# QFP_32U4.net
KiCad netlist of a schematic drawn in EAGLE
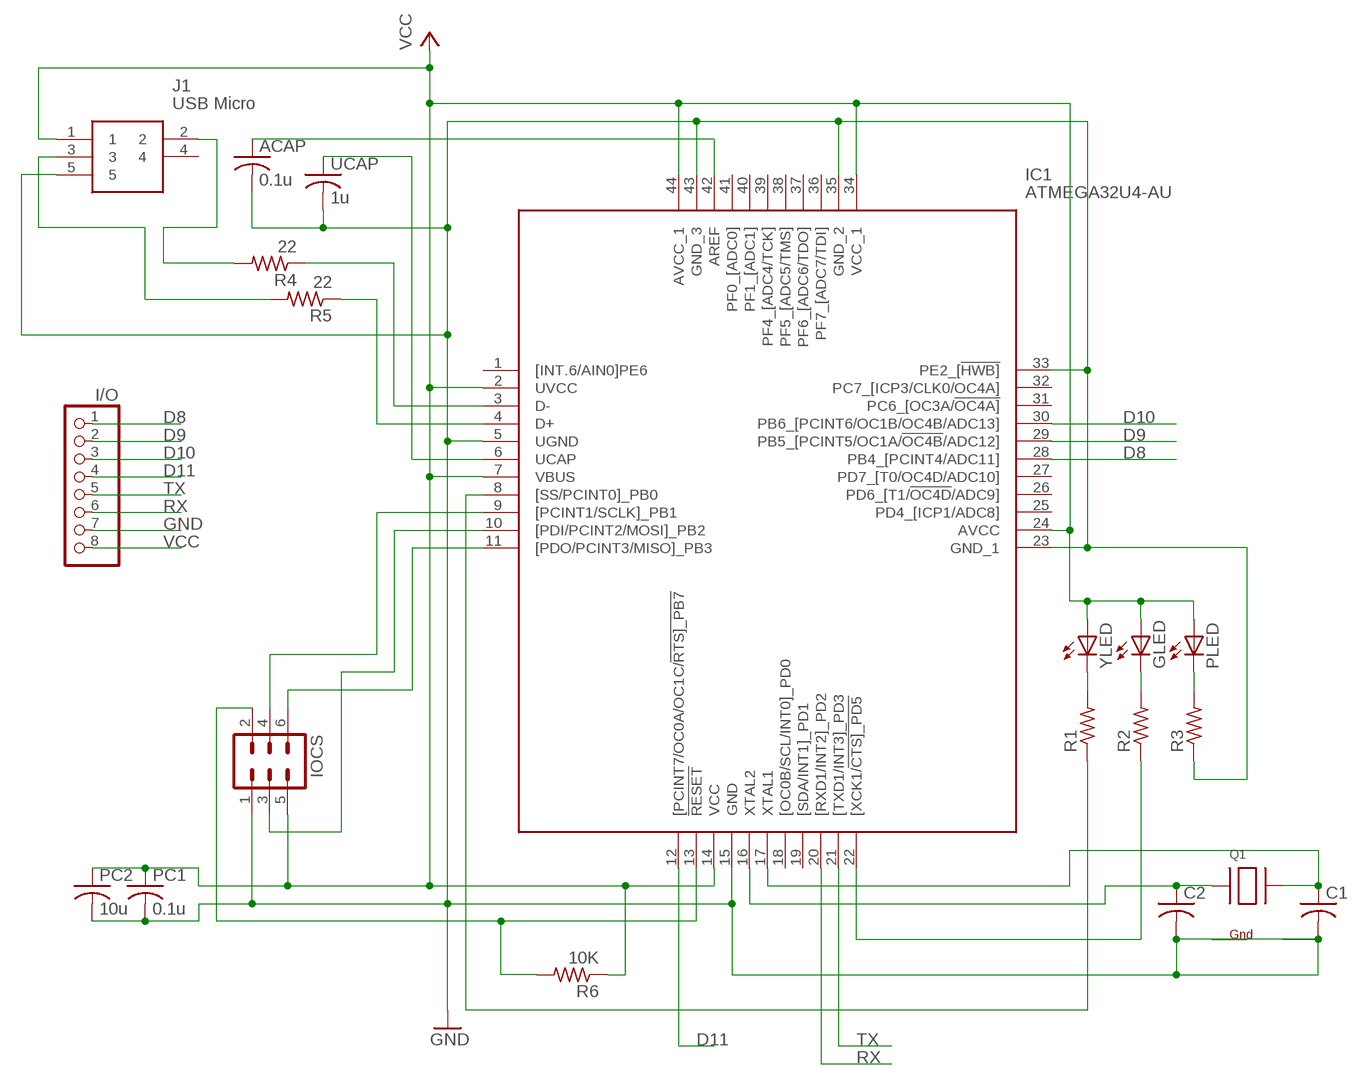
[diagram p0: schematic, sheet 1]

(export (version "E")
  (design (tool "Eeschema 10.0.6"))
  (components
    (comp (ref "ACAP")
      (value "0.1u")
      (footprint "eagle-import:C0805")
      (libsource (lib "eagle-import") (part "C-USC0805"))
    )
    (comp (ref "C1")
      (value "C-USC0805")
      (footprint "eagle-import:C0805")
      (libsource (lib "eagle-import") (part "C-USC0805"))
    )
    (comp (ref "C2")
      (value "C-USC0805")
      (footprint "eagle-import:C0805")
      (libsource (lib "eagle-import") (part "C-USC0805"))
    )
    (comp (ref "GLED")
      (value "LEDCHIP-LED0805")
      (footprint "eagle-import:CHIP-LED0805")
      (libsource (lib "eagle-import") (part "LEDCHIP-LED0805"))
    )
    (comp (ref "I/O")
      (value "PINHD-1X8CLEANBIG")
      (footprint "eagle-import:1X08-CLEANBIG")
      (libsource (lib "eagle-import") (part "PINHD-1X8CLEANBIG"))
    )
    (comp (ref "IC1")
      (value "ATMEGA32U4-AU")
      (footprint "eagle-import:QFP80P1200X1200X120-44N")
      (fields (field (name "RS_PART_NUMBER") "1310289P"))
      (libsource (lib "eagle-import") (part "ATMEGA32U4-AU"))
    )
    (comp (ref "IOCS")
      (value "MA03-2")
      (footprint "eagle-import:MA03-2")
      (libsource (lib "eagle-import") (part "MA03-2"))
    )
    (comp (ref "J1")
      (value "USB Micro")
      (footprint "eagle-import:10104110-0001LF")
      (fields (field (name "ARROW_PART_NUMBER") "10104110-0001LF") (field (name "RS_PART_NUMBER") "1738645"))
      (libsource (lib "eagle-import") (part "10104110-0001LF"))
    )
    (comp (ref "PC1")
      (value "0.1u")
      (footprint "eagle-import:C0805")
      (libsource (lib "eagle-import") (part "C-USC0805"))
    )
    (comp (ref "PC2")
      (value "10u")
      (footprint "eagle-import:C0805")
      (libsource (lib "eagle-import") (part "C-USC0805"))
    )
    (comp (ref "PLED")
      (value "LEDCHIP-LED0805")
      (footprint "eagle-import:CHIP-LED0805")
      (libsource (lib "eagle-import") (part "LEDCHIP-LED0805"))
    )
    (comp (ref "Q1")
      (value "XTAL-4-3225")
      (footprint "eagle-import:NX3225")
      (libsource (lib "eagle-import") (part "XTAL-4-3225"))
    )
    (comp (ref "R1")
      (value "R-US_M0805")
      (footprint "eagle-import:M0805")
      (libsource (lib "eagle-import") (part "R-US_M0805"))
    )
    (comp (ref "R2")
      (value "R-US_M0805")
      (footprint "eagle-import:M0805")
      (libsource (lib "eagle-import") (part "R-US_M0805"))
    )
    (comp (ref "R3")
      (value "R-US_M0805")
      (footprint "eagle-import:M0805")
      (libsource (lib "eagle-import") (part "R-US_M0805"))
    )
    (comp (ref "R4")
      (value "22")
      (footprint "eagle-import:M0805")
      (libsource (lib "eagle-import") (part "R-US_M0805"))
    )
    (comp (ref "R5")
      (value "22")
      (footprint "eagle-import:M0805")
      (libsource (lib "eagle-import") (part "R-US_M0805"))
    )
    (comp (ref "R6")
      (value "10K")
      (footprint "eagle-import:M0805")
      (libsource (lib "eagle-import") (part "R-US_M0805"))
    )
    (comp (ref "UCAP")
      (value "1u")
      (footprint "eagle-import:C0805")
      (libsource (lib "eagle-import") (part "C-USC0805"))
    )
    (comp (ref "YLED")
      (value "LEDCHIP-LED0805")
      (footprint "eagle-import:CHIP-LED0805")
      (libsource (lib "eagle-import") (part "LEDCHIP-LED0805"))
    )
  )
  (nets
    (net (code "1") (name "/D8") (class "Default")
      (node (ref "I/O") (pin "1") (pinfunction "1_1") (pintype "passive"))
      (node (ref "IC1") (pin "28") (pinfunction "PB4_[PCINT4/ADC11]_28") (pintype "input"))
    )
    (net (code "2") (name "/D9") (class "Default")
      (node (ref "I/O") (pin "2") (pinfunction "2_2") (pintype "passive"))
      (node (ref "IC1") (pin "29") (pinfunction "PB5_[PCINT5/OC1A/~{OC4B}/ADC12]_29") (pintype "input"))
    )
    (net (code "3") (name "/D10") (class "Default")
      (node (ref "I/O") (pin "3") (pinfunction "3_3") (pintype "passive"))
      (node (ref "IC1") (pin "30") (pinfunction "PB6_[PCINT6/OC1B/OC4B/ADC13]_30") (pintype "input"))
    )
    (net (code "4") (name "/D11") (class "Default")
      (node (ref "I/O") (pin "4") (pinfunction "4_4") (pintype "passive"))
      (node (ref "IC1") (pin "12") (pinfunction "[PCINT7/OC0A/OC1C/~{RTS]_PB7}_12") (pintype "input"))
    )
    (net (code "5") (name "/RX") (class "Default")
      (node (ref "I/O") (pin "6") (pinfunction "6_6") (pintype "passive"))
      (node (ref "IC1") (pin "20") (pinfunction "[RXD1/INT2]_PD2_20") (pintype "input"))
    )
    (net (code "6") (name "/TX") (class "Default")
      (node (ref "I/O") (pin "5") (pinfunction "5_5") (pintype "passive"))
      (node (ref "IC1") (pin "21") (pinfunction "[TXD1/INT3]_PD3_21") (pintype "input"))
    )
    (net (code "7") (name "GND") (class "Default")
      (node (ref "ACAP") (pin "2") (pinfunction "2_2") (pintype "passive"))
      (node (ref "C1") (pin "2") (pinfunction "2_2") (pintype "passive"))
      (node (ref "C2") (pin "2") (pinfunction "2_2") (pintype "passive"))
      (node (ref "I/O") (pin "7") (pinfunction "7_7") (pintype "passive"))
      (node (ref "IC1") (pin "15") (pinfunction "GND_15") (pintype "power_in"))
      (node (ref "IC1") (pin "23") (pinfunction "GND_1_23") (pintype "power_in"))
      (node (ref "IC1") (pin "33") (pinfunction "PE2_[~{HWB]}_33") (pintype "bidirectional"))
      (node (ref "IC1") (pin "35") (pinfunction "GND_2_35") (pintype "power_in"))
      (node (ref "IC1") (pin "43") (pinfunction "GND_3_43") (pintype "power_in"))
      (node (ref "IC1") (pin "5") (pinfunction "UGND_5") (pintype "power_in"))
      (node (ref "IOCS") (pin "1") (pinfunction "1_1") (pintype "passive"))
      (node (ref "J1") (pin "5") (pinfunction "5_5") (pintype "bidirectional"))
      (node (ref "PC1") (pin "2") (pinfunction "2_2") (pintype "passive"))
      (node (ref "PC2") (pin "2") (pinfunction "2_2") (pintype "passive"))
      (node (ref "Q1") (pin "2") (pinfunction "G2_2") (pintype "power_in"))
      (node (ref "Q1") (pin "4") (pinfunction "G1_4") (pintype "power_in"))
      (node (ref "R3") (pin "1") (pinfunction "1_1") (pintype "passive"))
      (node (ref "UCAP") (pin "2") (pinfunction "2_2") (pintype "passive"))
    )
    (net (code "8") (name "Net-(GLED-PadC)") (class "Default")
      (node (ref "GLED") (pin "C") (pinfunction "C_C") (pintype "passive"))
      (node (ref "R2") (pin "2") (pinfunction "2_2") (pintype "passive"))
    )
    (net (code "9") (name "Net-(IC1-AREF)") (class "Default")
      (node (ref "ACAP") (pin "1") (pinfunction "1_1") (pintype "passive"))
      (node (ref "IC1") (pin "42") (pinfunction "AREF_42") (pintype "input"))
    )
    (net (code "10") (name "Net-(IC1-D+)") (class "Default")
      (node (ref "IC1") (pin "4") (pinfunction "D+_4") (pintype "bidirectional"))
      (node (ref "R5") (pin "1") (pinfunction "1_1") (pintype "passive"))
    )
    (net (code "11") (name "Net-(IC1-D-)") (class "Default")
      (node (ref "IC1") (pin "3") (pinfunction "D-_3") (pintype "bidirectional"))
      (node (ref "R4") (pin "1") (pinfunction "1_1") (pintype "passive"))
    )
    (net (code "12") (name "Net-(IC1-UCAP)") (class "Default")
      (node (ref "IC1") (pin "6") (pinfunction "UCAP_6") (pintype "bidirectional"))
      (node (ref "UCAP") (pin "1") (pinfunction "1_1") (pintype "passive"))
    )
    (net (code "13") (name "Net-(IC1-XTAL1)") (class "Default")
      (node (ref "C1") (pin "1") (pinfunction "1_1") (pintype "passive"))
      (node (ref "IC1") (pin "17") (pinfunction "XTAL1_17") (pintype "bidirectional"))
      (node (ref "Q1") (pin "3") (pinfunction "X2_3") (pintype "bidirectional"))
    )
    (net (code "14") (name "Net-(IC1-XTAL2)") (class "Default")
      (node (ref "C2") (pin "1") (pinfunction "1_1") (pintype "passive"))
      (node (ref "IC1") (pin "16") (pinfunction "XTAL2_16") (pintype "bidirectional"))
      (node (ref "Q1") (pin "1") (pinfunction "X1_1") (pintype "bidirectional"))
    )
    (net (code "15") (name "Net-(IC1-[PCINT1{slash}SCLK]_PB1)") (class "Default")
      (node (ref "IC1") (pin "9") (pinfunction "[PCINT1/SCLK]_PB1_9") (pintype "input"))
      (node (ref "IOCS") (pin "4") (pinfunction "4_4") (pintype "passive"))
    )
    (net (code "16") (name "Net-(IC1-[PDI{slash}PCINT2{slash}MOSI]_PB2)") (class "Default")
      (node (ref "IC1") (pin "10") (pinfunction "[PDI/PCINT2/MOSI]_PB2_10") (pintype "input"))
      (node (ref "IOCS") (pin "3") (pinfunction "3_3") (pintype "passive"))
    )
    (net (code "17") (name "Net-(IC1-[PDO{slash}PCINT3{slash}MISO]_PB3)") (class "Default")
      (node (ref "IC1") (pin "11") (pinfunction "[PDO/PCINT3/MISO]_PB3_11") (pintype "input"))
      (node (ref "IOCS") (pin "6") (pinfunction "6_6") (pintype "passive"))
    )
    (net (code "18") (name "Net-(IC1-[SS{slash}PCINT0]_PB0)") (class "Default")
      (node (ref "IC1") (pin "8") (pinfunction "[SS/PCINT0]_PB0_8") (pintype "input"))
      (node (ref "R1") (pin "1") (pinfunction "1_1") (pintype "passive"))
    )
    (net (code "19") (name "Net-(IC1-[XCK1{slash}~{CTS]_PD5})") (class "Default")
      (node (ref "IC1") (pin "22") (pinfunction "[XCK1/~{CTS]_PD5}_22") (pintype "bidirectional"))
      (node (ref "R2") (pin "1") (pinfunction "1_1") (pintype "passive"))
    )
    (net (code "20") (name "Net-(IC1-~{RESET})") (class "Default")
      (node (ref "IC1") (pin "13") (pinfunction "~{RESET}_13") (pintype "bidirectional"))
      (node (ref "IOCS") (pin "2") (pinfunction "2_2") (pintype "passive"))
      (node (ref "R6") (pin "2") (pinfunction "2_2") (pintype "passive"))
    )
    (net (code "21") (name "Net-(J1-Pad2)") (class "Default")
      (node (ref "J1") (pin "2") (pinfunction "2_2") (pintype "bidirectional"))
      (node (ref "R4") (pin "2") (pinfunction "2_2") (pintype "passive"))
    )
    (net (code "22") (name "Net-(J1-Pad3)") (class "Default")
      (node (ref "J1") (pin "3") (pinfunction "3_3") (pintype "bidirectional"))
      (node (ref "R5") (pin "2") (pinfunction "2_2") (pintype "passive"))
    )
    (net (code "23") (name "Net-(PLED-PadC)") (class "Default")
      (node (ref "PLED") (pin "C") (pinfunction "C_C") (pintype "passive"))
      (node (ref "R3") (pin "2") (pinfunction "2_2") (pintype "passive"))
    )
    (net (code "24") (name "Net-(R1-Pad2)") (class "Default")
      (node (ref "R1") (pin "2") (pinfunction "2_2") (pintype "passive"))
      (node (ref "YLED") (pin "C") (pinfunction "C_C") (pintype "passive"))
    )
    (net (code "25") (name "VCC") (class "Default")
      (node (ref "GLED") (pin "A") (pinfunction "A_A") (pintype "passive"))
      (node (ref "I/O") (pin "8") (pinfunction "8_8") (pintype "passive"))
      (node (ref "IC1") (pin "14") (pinfunction "VCC_14") (pintype "power_in"))
      (node (ref "IC1") (pin "2") (pinfunction "UVCC_2") (pintype "power_in"))
      (node (ref "IC1") (pin "24") (pinfunction "AVCC_24") (pintype "power_in"))
      (node (ref "IC1") (pin "34") (pinfunction "VCC_1_34") (pintype "power_in"))
      (node (ref "IC1") (pin "44") (pinfunction "AVCC_1_44") (pintype "power_in"))
      (node (ref "IC1") (pin "7") (pinfunction "VBUS_7") (pintype "bidirectional"))
      (node (ref "IOCS") (pin "5") (pinfunction "5_5") (pintype "passive"))
      (node (ref "J1") (pin "1") (pinfunction "1_1") (pintype "bidirectional"))
      (node (ref "PC1") (pin "1") (pinfunction "1_1") (pintype "passive"))
      (node (ref "PC2") (pin "1") (pinfunction "1_1") (pintype "passive"))
      (node (ref "PLED") (pin "A") (pinfunction "A_A") (pintype "passive"))
      (node (ref "R6") (pin "1") (pinfunction "1_1") (pintype "passive"))
      (node (ref "YLED") (pin "A") (pinfunction "A_A") (pintype "passive"))
    )
    (net (code "26") (name "unconnected-(IC1-PC6_[OC3A{slash}~{OC4A]}-Pad31)") (class "Default")
      (node (ref "IC1") (pin "31") (pinfunction "PC6_[OC3A/~{OC4A]}_31") (pintype "bidirectional"))
    )
    (net (code "27") (name "unconnected-(IC1-PC7_[ICP3{slash}CLK0{slash}OC4A]-Pad32)") (class "Default")
      (node (ref "IC1") (pin "32") (pinfunction "PC7_[ICP3/CLK0/OC4A]_32") (pintype "input"))
    )
    (net (code "28") (name "unconnected-(IC1-PD4_[ICP1{slash}ADC8]-Pad25)") (class "Default")
      (node (ref "IC1") (pin "25") (pinfunction "PD4_[ICP1/ADC8]_25") (pintype "bidirectional"))
    )
    (net (code "29") (name "unconnected-(IC1-PD6_[T1{slash}~{OC4D}{slash}ADC9]-Pad26)") (class "Default")
      (node (ref "IC1") (pin "26") (pinfunction "PD6_[T1/~{OC4D}/ADC9]_26") (pintype "bidirectional"))
    )
    (net (code "30") (name "unconnected-(IC1-PD7_[T0{slash}OC4D{slash}ADC10]-Pad27)") (class "Default")
      (node (ref "IC1") (pin "27") (pinfunction "PD7_[T0/OC4D/ADC10]_27") (pintype "bidirectional"))
    )
    (net (code "31") (name "unconnected-(IC1-PF0_[ADC0]-Pad41)") (class "Default")
      (node (ref "IC1") (pin "41") (pinfunction "PF0_[ADC0]_41") (pintype "bidirectional"))
    )
    (net (code "32") (name "unconnected-(IC1-PF1_[ADC1]-Pad40)") (class "Default")
      (node (ref "IC1") (pin "40") (pinfunction "PF1_[ADC1]_40") (pintype "bidirectional"))
    )
    (net (code "33") (name "unconnected-(IC1-PF4_[ADC4{slash}TCK]-Pad39)") (class "Default")
      (node (ref "IC1") (pin "39") (pinfunction "PF4_[ADC4/TCK]_39") (pintype "bidirectional"))
    )
    (net (code "34") (name "unconnected-(IC1-PF5_[ADC5{slash}TMS]-Pad38)") (class "Default")
      (node (ref "IC1") (pin "38") (pinfunction "PF5_[ADC5/TMS]_38") (pintype "bidirectional"))
    )
    (net (code "35") (name "unconnected-(IC1-PF6_[ADC6{slash}TDO]-Pad37)") (class "Default")
      (node (ref "IC1") (pin "37") (pinfunction "PF6_[ADC6/TDO]_37") (pintype "bidirectional"))
    )
    (net (code "36") (name "unconnected-(IC1-PF7_[ADC7{slash}TDI]-Pad36)") (class "Default")
      (node (ref "IC1") (pin "36") (pinfunction "PF7_[ADC7/TDI]_36") (pintype "bidirectional"))
    )
    (net (code "37") (name "unconnected-(IC1-[INT.6{slash}AIN0]PE6-Pad1)") (class "Default")
      (node (ref "IC1") (pin "1") (pinfunction "[INT.6/AIN0]PE6_1") (pintype "input"))
    )
    (net (code "38") (name "unconnected-(IC1-[OC0B{slash}SCL{slash}INT0]_PD0-Pad18)") (class "Default")
      (node (ref "IC1") (pin "18") (pinfunction "[OC0B/SCL/INT0]_PD0_18") (pintype "input"))
    )
    (net (code "39") (name "unconnected-(IC1-[SDA{slash}INT1]_PD1-Pad19)") (class "Default")
      (node (ref "IC1") (pin "19") (pinfunction "[SDA/INT1]_PD1_19") (pintype "input"))
    )
    (net (code "40") (name "unconnected-(J1-Pad4)") (class "Default")
      (node (ref "J1") (pin "4") (pinfunction "4_4") (pintype "bidirectional"))
    )
  )
)
